# can4vscp_usb_rev_B.net
KiCad netlist of a schematic drawn in EAGLE
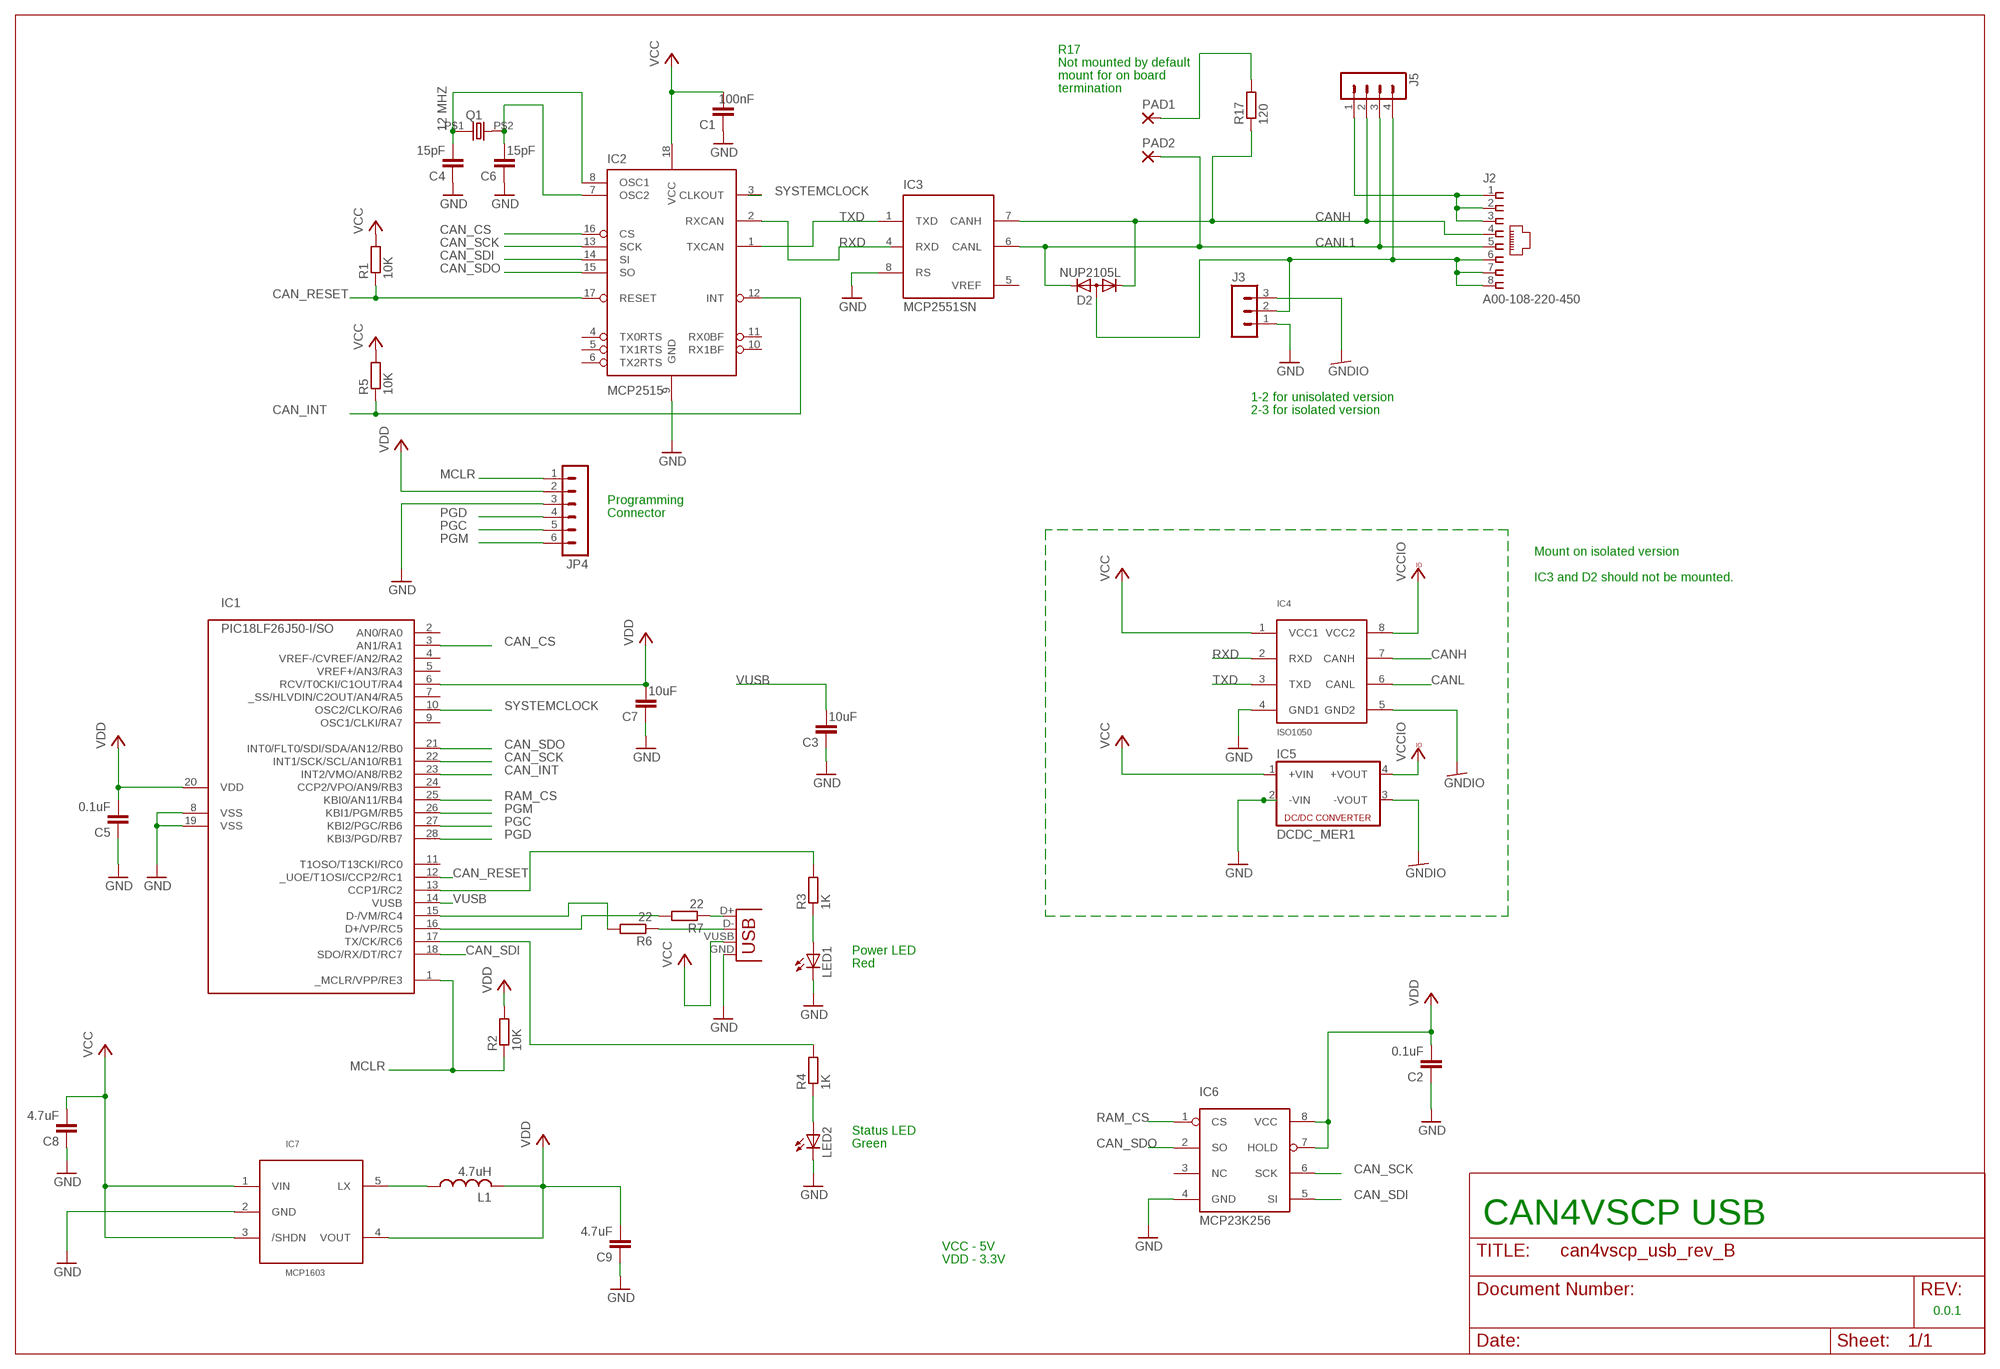
[diagram p0: schematic, sheet 1]

(export (version "E")
  (design (tool "Eeschema 10.0.6"))
  (components
    (comp (ref "C1")
      (value "100nF")
      (footprint "eagle-import:C0805")
      (libsource (lib "eagle-import") (part "C-EUC0805"))
    )
    (comp (ref "C2")
      (value "0.1uF")
      (footprint "eagle-import:C0805")
      (libsource (lib "eagle-import") (part "C-EUC0805"))
    )
    (comp (ref "C3")
      (value "10uF")
      (footprint "eagle-import:C0805")
      (libsource (lib "eagle-import") (part "C-EUC0805"))
    )
    (comp (ref "C4")
      (value "15pF")
      (footprint "eagle-import:C0805")
      (libsource (lib "eagle-import") (part "C-EUC0805"))
    )
    (comp (ref "C5")
      (value "0.1uF")
      (footprint "eagle-import:C0805")
      (libsource (lib "eagle-import") (part "C-EUC0805"))
    )
    (comp (ref "C6")
      (value "15pF")
      (footprint "eagle-import:C0805")
      (libsource (lib "eagle-import") (part "C-EUC0805"))
    )
    (comp (ref "C7")
      (value "10uF")
      (footprint "eagle-import:C0805")
      (libsource (lib "eagle-import") (part "C-EUC0805"))
    )
    (comp (ref "C8")
      (value "4.7uF")
      (footprint "eagle-import:C0805")
      (libsource (lib "eagle-import") (part "C-EUC0805"))
    )
    (comp (ref "C9")
      (value "4.7uF")
      (footprint "eagle-import:C0805")
      (libsource (lib "eagle-import") (part "C-EUC0805"))
    )
    (comp (ref "D2")
      (value "NUP2105L")
      (footprint "eagle-import:SOT23")
      (libsource (lib "eagle-import") (part "DIODE-2CA|ACSOT23"))
    )
    (comp (ref "IC1")
      (value "PIC18LF26J50-I/SO")
      (footprint "eagle-import:SO-28W")
      (libsource (lib "eagle-import") (part "PIC182550-I/SOLF"))
    )
    (comp (ref "IC2")
      (value "MCP2515")
      (footprint "eagle-import:SO-18W")
      (libsource (lib "eagle-import") (part "MCP2515"))
    )
    (comp (ref "IC3")
      (value "MCP2551SN")
      (footprint "eagle-import:SO-08")
      (libsource (lib "eagle-import") (part "MCP2551SN"))
    )
    (comp (ref "IC4")
      (value "ISO1050")
      (footprint "eagle-import:DUB_PSOP")
      (libsource (lib "eagle-import") (part "ISO1050"))
    )
    (comp (ref "IC5")
      (value "DCDC_MER1")
      (footprint "eagle-import:MER1")
      (libsource (lib "eagle-import") (part "DCDC_MER1"))
    )
    (comp (ref "IC6")
      (value "MCP23K256")
      (footprint "eagle-import:SO-8")
      (libsource (lib "eagle-import") (part "MCP23A256"))
    )
    (comp (ref "IC7")
      (value "MCP1603")
      (footprint "eagle-import:SOT23-5L")
      (libsource (lib "eagle-import") (part "MCP1603"))
    )
    (comp (ref "J2")
      (value "A00-108-220-450")
      (footprint "eagle-import:RJ-45")
      (libsource (lib "eagle-import") (part "A00-108-220-450"))
    )
    (comp (ref "J3")
      (value "MA03-1")
      (footprint "eagle-import:MA03-1")
      (libsource (lib "eagle-import") (part "MA03-1"))
    )
    (comp (ref "J4")
      (value "USB-B-S")
      (footprint "eagle-import:USB-B-SMT")
      (libsource (lib "eagle-import") (part "USB-B-S"))
    )
    (comp (ref "J5")
      (value "MA04-1")
      (footprint "eagle-import:MA04-1")
      (libsource (lib "eagle-import") (part "MA04-1"))
    )
    (comp (ref "JP4")
      (value "MA06-1")
      (footprint "eagle-import:MA06-1")
      (libsource (lib "eagle-import") (part "MA06-1"))
    )
    (comp (ref "L1")
      (value "4.7uH")
      (footprint "eagle-import:L2012C")
      (libsource (lib "eagle-import") (part "L-USL2012C"))
    )
    (comp (ref "LED1")
      (value "LEDCHIP-LED0805")
      (footprint "eagle-import:CHIP-LED0805")
      (libsource (lib "eagle-import") (part "LEDCHIP-LED0805"))
    )
    (comp (ref "LED2")
      (value "LEDCHIP-LED0805")
      (footprint "eagle-import:CHIP-LED0805")
      (libsource (lib "eagle-import") (part "LEDCHIP-LED0805"))
    )
    (comp (ref "PAD1")
      (value "1,6/0,8")
      (footprint "eagle-import:1,6_0,8")
      (libsource (lib "eagle-import") (part "1,6/0,8"))
    )
    (comp (ref "PAD2")
      (value "1,6/0,8")
      (footprint "eagle-import:1,6_0,8")
      (libsource (lib "eagle-import") (part "1,6/0,8"))
    )
    (comp (ref "Q1")
      (value "12 MHZ")
      (footprint "eagle-import:9C")
      (libsource (lib "eagle-import") (part "HC-49S"))
    )
    (comp (ref "R1")
      (value "10K")
      (footprint "eagle-import:R0805")
      (libsource (lib "eagle-import") (part "R-EU_R0805"))
    )
    (comp (ref "R2")
      (value "10K")
      (footprint "eagle-import:R0805")
      (libsource (lib "eagle-import") (part "R-EU_R0805"))
    )
    (comp (ref "R3")
      (value "1K")
      (footprint "eagle-import:R0805")
      (libsource (lib "eagle-import") (part "R-EU_R0805"))
    )
    (comp (ref "R4")
      (value "1K")
      (footprint "eagle-import:R0805")
      (libsource (lib "eagle-import") (part "R-EU_R0805"))
    )
    (comp (ref "R5")
      (value "10K")
      (footprint "eagle-import:R0805")
      (libsource (lib "eagle-import") (part "R-EU_R0805"))
    )
    (comp (ref "R6")
      (value "22")
      (footprint "eagle-import:R0805")
      (libsource (lib "eagle-import") (part "R-EU_R0805"))
    )
    (comp (ref "R7")
      (value "22")
      (footprint "eagle-import:R0805")
      (libsource (lib "eagle-import") (part "R-EU_R0805"))
    )
    (comp (ref "R17")
      (value "120")
      (footprint "eagle-import:R0805")
      (libsource (lib "eagle-import") (part "R-EU_R0805"))
    )
  )
  (nets
    (net (code "1") (name "/CANH") (class "Default")
      (node (ref "D2") (pin "1") (pinfunction "K1_1") (pintype "passive"))
      (node (ref "IC3") (pin "7") (pinfunction "CANH_7") (pintype "bidirectional"))
      (node (ref "IC4") (pin "7") (pinfunction "CANH_7") (pintype "bidirectional"))
      (node (ref "J2") (pin "4") (pinfunction "4_4") (pintype "passive"))
      (node (ref "J5") (pin "2") (pinfunction "2_2") (pintype "passive"))
      (node (ref "R17") (pin "1") (pinfunction "1_1") (pintype "passive"))
    )
    (net (code "2") (name "/CANL") (class "Default")
      (node (ref "IC4") (pin "6") (pinfunction "CANL_6") (pintype "bidirectional"))
    )
    (net (code "3") (name "/CANL1") (class "Default")
      (node (ref "D2") (pin "2") (pinfunction "K2_2") (pintype "passive"))
      (node (ref "IC3") (pin "6") (pinfunction "CANL_6") (pintype "bidirectional"))
      (node (ref "J2") (pin "5") (pinfunction "5_5") (pintype "passive"))
      (node (ref "J5") (pin "3") (pinfunction "3_3") (pintype "passive"))
      (node (ref "PAD2") (pin "1") (pinfunction "P_1") (pintype "passive"))
    )
    (net (code "4") (name "/CAN_CS") (class "Default")
      (node (ref "IC1") (pin "3") (pinfunction "AN1/RA1_3") (pintype "bidirectional"))
      (node (ref "IC2") (pin "16") (pinfunction "CS_16") (pintype "input"))
    )
    (net (code "5") (name "/CAN_INT") (class "Default")
      (node (ref "IC1") (pin "23") (pinfunction "INT2/VMO/AN8/RB2_23") (pintype "bidirectional"))
      (node (ref "IC2") (pin "12") (pinfunction "INT_12") (pintype "output"))
      (node (ref "R5") (pin "1") (pinfunction "1_1") (pintype "passive"))
    )
    (net (code "6") (name "/CAN_RESET") (class "Default")
      (node (ref "IC1") (pin "12") (pinfunction "_UOE/T1OSI/CCP2/RC1_12") (pintype "bidirectional"))
      (node (ref "IC2") (pin "17") (pinfunction "RESET_17") (pintype "input"))
      (node (ref "R1") (pin "1") (pinfunction "1_1") (pintype "passive"))
    )
    (net (code "7") (name "/CAN_SCK") (class "Default")
      (node (ref "IC1") (pin "22") (pinfunction "INT1/SCK/SCL/AN10/RB1_22") (pintype "bidirectional"))
      (node (ref "IC2") (pin "13") (pinfunction "SCK_13") (pintype "input"))
      (node (ref "IC6") (pin "6") (pinfunction "SCK_6") (pintype "input"))
    )
    (net (code "8") (name "/CAN_SDI") (class "Default")
      (node (ref "IC1") (pin "18") (pinfunction "SDO/RX/DT/RC7_18") (pintype "bidirectional"))
      (node (ref "IC2") (pin "14") (pinfunction "SI_14") (pintype "input"))
      (node (ref "IC6") (pin "5") (pinfunction "SI_5") (pintype "input"))
    )
    (net (code "9") (name "/CAN_SDO") (class "Default")
      (node (ref "IC1") (pin "21") (pinfunction "INT0/FLT0/SDI/SDA/AN12/RB0_21") (pintype "bidirectional"))
      (node (ref "IC2") (pin "15") (pinfunction "SO_15") (pintype "output"))
      (node (ref "IC6") (pin "2") (pinfunction "SO_2") (pintype "output"))
    )
    (net (code "10") (name "/MCLR") (class "Default")
      (node (ref "IC1") (pin "1") (pinfunction "_MCLR/VPP/RE3_1") (pintype "input"))
      (node (ref "JP4") (pin "1") (pinfunction "1_1") (pintype "passive"))
      (node (ref "R2") (pin "1") (pinfunction "1_1") (pintype "passive"))
    )
    (net (code "11") (name "/PGC") (class "Default")
      (node (ref "IC1") (pin "27") (pinfunction "KBI2/PGC/RB6_27") (pintype "bidirectional"))
      (node (ref "JP4") (pin "5") (pinfunction "5_5") (pintype "passive"))
    )
    (net (code "12") (name "/PGD") (class "Default")
      (node (ref "IC1") (pin "28") (pinfunction "KBI3/PGD/RB7_28") (pintype "bidirectional"))
      (node (ref "JP4") (pin "4") (pinfunction "4_4") (pintype "passive"))
    )
    (net (code "13") (name "/PGM") (class "Default")
      (node (ref "IC1") (pin "26") (pinfunction "KBI1/PGM/RB5_26") (pintype "bidirectional"))
      (node (ref "JP4") (pin "6") (pinfunction "6_6") (pintype "passive"))
    )
    (net (code "14") (name "/RAM_CS") (class "Default")
      (node (ref "IC1") (pin "25") (pinfunction "KBI0/AN11/RB4_25") (pintype "bidirectional"))
      (node (ref "IC6") (pin "1") (pinfunction "CS_1") (pintype "input"))
    )
    (net (code "15") (name "/RXD") (class "Default")
      (node (ref "IC2") (pin "2") (pinfunction "RXCAN_2") (pintype "input"))
      (node (ref "IC4") (pin "2") (pinfunction "RXD_2") (pintype "bidirectional"))
    )
    (net (code "16") (name "/SYSTEMCLOCK") (class "Default")
      (node (ref "IC1") (pin "10") (pinfunction "OSC2/CLKO/RA6_10") (pintype "bidirectional"))
      (node (ref "IC2") (pin "3") (pinfunction "CLKOUT_3") (pintype "output"))
    )
    (net (code "17") (name "/TXD") (class "Default")
      (node (ref "IC2") (pin "1") (pinfunction "TXCAN_1") (pintype "output"))
      (node (ref "IC3") (pin "1") (pinfunction "TXD_1") (pintype "input"))
      (node (ref "IC4") (pin "3") (pinfunction "TXD_3") (pintype "bidirectional"))
    )
    (net (code "18") (name "/VREF") (class "Default")
      (node (ref "IC3") (pin "5") (pinfunction "VREF_5") (pintype "power_in"))
    )
    (net (code "19") (name "/VUSB") (class "Default")
      (node (ref "C3") (pin "2") (pinfunction "2_2") (pintype "passive"))
      (node (ref "IC1") (pin "14") (pinfunction "VUSB_14") (pintype "bidirectional"))
    )
    (net (code "20") (name "GND") (class "Default")
      (node (ref "C1") (pin "1") (pinfunction "1_1") (pintype "passive"))
      (node (ref "C2") (pin "1") (pinfunction "1_1") (pintype "passive"))
      (node (ref "C3") (pin "1") (pinfunction "1_1") (pintype "passive"))
      (node (ref "C4") (pin "1") (pinfunction "1_1") (pintype "passive"))
      (node (ref "C5") (pin "1") (pinfunction "1_1") (pintype "passive"))
      (node (ref "C6") (pin "1") (pinfunction "1_1") (pintype "passive"))
      (node (ref "C7") (pin "1") (pinfunction "1_1") (pintype "passive"))
      (node (ref "C8") (pin "1") (pinfunction "1_1") (pintype "passive"))
      (node (ref "C9") (pin "1") (pinfunction "1_1") (pintype "passive"))
      (node (ref "IC1") (pin "19") (pinfunction "VSS_19") (pintype "power_in"))
      (node (ref "IC1") (pin "8") (pinfunction "VSS_8") (pintype "power_in"))
      (node (ref "IC2") (pin "9") (pinfunction "GND_9") (pintype "power_in"))
      (node (ref "IC3") (pin "8") (pinfunction "RS_8") (pintype "input"))
      (node (ref "IC4") (pin "4") (pinfunction "GND1_4") (pintype "power_in"))
      (node (ref "IC5") (pin "2") (pinfunction "-VIN_2") (pintype "passive"))
      (node (ref "IC6") (pin "4") (pinfunction "GND_4") (pintype "power_in"))
      (node (ref "IC7") (pin "2") (pinfunction "GND_2") (pintype "power_in"))
      (node (ref "J3") (pin "1") (pinfunction "1_1") (pintype "passive"))
      (node (ref "J4") (pin "GND") (pinfunction "GND_GND") (pintype "bidirectional"))
      (node (ref "JP4") (pin "3") (pinfunction "3_3") (pintype "passive"))
      (node (ref "LED1") (pin "C") (pinfunction "C_C") (pintype "passive"))
      (node (ref "LED2") (pin "C") (pinfunction "C_C") (pintype "passive"))
    )
    (net (code "21") (name "GNDIO") (class "Default")
      (node (ref "IC4") (pin "5") (pinfunction "GND2_5") (pintype "power_in"))
      (node (ref "IC5") (pin "3") (pinfunction "-VOUT_3") (pintype "passive"))
      (node (ref "J3") (pin "3") (pinfunction "3_3") (pintype "passive"))
    )
    (net (code "22") (name "Net-(D2-A)") (class "Default")
      (node (ref "D2") (pin "3") (pinfunction "A_3") (pintype "passive"))
      (node (ref "J2") (pin "6") (pinfunction "6_6") (pintype "passive"))
      (node (ref "J2") (pin "7") (pinfunction "7_7") (pintype "passive"))
      (node (ref "J2") (pin "8") (pinfunction "8_8") (pintype "passive"))
      (node (ref "J3") (pin "2") (pinfunction "2_2") (pintype "passive"))
      (node (ref "J5") (pin "4") (pinfunction "4_4") (pintype "passive"))
    )
    (net (code "23") (name "Net-(IC1-CCP1{slash}RC2)") (class "Default")
      (node (ref "IC1") (pin "13") (pinfunction "CCP1/RC2_13") (pintype "bidirectional"))
      (node (ref "R3") (pin "2") (pinfunction "2_2") (pintype "passive"))
    )
    (net (code "24") (name "Net-(IC1-D+{slash}VP{slash}RC5)") (class "Default")
      (node (ref "IC1") (pin "16") (pinfunction "D+/VP/RC5_16") (pintype "bidirectional"))
      (node (ref "R7") (pin "2") (pinfunction "2_2") (pintype "passive"))
    )
    (net (code "25") (name "Net-(IC1-D-{slash}VM{slash}RC4)") (class "Default")
      (node (ref "IC1") (pin "15") (pinfunction "D-/VM/RC4_15") (pintype "bidirectional"))
      (node (ref "R6") (pin "2") (pinfunction "2_2") (pintype "passive"))
    )
    (net (code "26") (name "Net-(IC1-TX{slash}CK{slash}RC6)") (class "Default")
      (node (ref "IC1") (pin "17") (pinfunction "TX/CK/RC6_17") (pintype "bidirectional"))
      (node (ref "R4") (pin "2") (pinfunction "2_2") (pintype "passive"))
    )
    (net (code "27") (name "Net-(IC2-OSC1)") (class "Default")
      (node (ref "C4") (pin "2") (pinfunction "2_2") (pintype "passive"))
      (node (ref "IC2") (pin "8") (pinfunction "OSC1_8") (pintype "input"))
      (node (ref "Q1") (pin "P$1") (pinfunction "1_P$1") (pintype "passive"))
    )
    (net (code "28") (name "Net-(IC2-OSC2)") (class "Default")
      (node (ref "C6") (pin "2") (pinfunction "2_2") (pintype "passive"))
      (node (ref "IC2") (pin "7") (pinfunction "OSC2_7") (pintype "output"))
      (node (ref "Q1") (pin "P$2") (pinfunction "2_P$2") (pintype "passive"))
    )
    (net (code "29") (name "Net-(IC7-LX)") (class "Default")
      (node (ref "IC7") (pin "5") (pinfunction "LX_5") (pintype "bidirectional"))
      (node (ref "L1") (pin "1") (pinfunction "1_1") (pintype "passive"))
    )
    (net (code "30") (name "Net-(J2-Pad1)") (class "Default")
      (node (ref "J2") (pin "1") (pinfunction "1_1") (pintype "passive"))
      (node (ref "J2") (pin "2") (pinfunction "2_2") (pintype "passive"))
      (node (ref "J2") (pin "3") (pinfunction "3_3") (pintype "passive"))
      (node (ref "J5") (pin "1") (pinfunction "1_1") (pintype "passive"))
    )
    (net (code "31") (name "Net-(J4-PadD+)") (class "Default")
      (node (ref "J4") (pin "D+") (pinfunction "D+_D+") (pintype "bidirectional"))
      (node (ref "R7") (pin "1") (pinfunction "1_1") (pintype "passive"))
    )
    (net (code "32") (name "Net-(J4-PadD-)") (class "Default")
      (node (ref "J4") (pin "D-") (pinfunction "D-_D-") (pintype "bidirectional"))
      (node (ref "R6") (pin "1") (pinfunction "1_1") (pintype "passive"))
    )
    (net (code "33") (name "Net-(LED1-PadA)") (class "Default")
      (node (ref "LED1") (pin "A") (pinfunction "A_A") (pintype "passive"))
      (node (ref "R3") (pin "1") (pinfunction "1_1") (pintype "passive"))
    )
    (net (code "34") (name "Net-(LED2-PadA)") (class "Default")
      (node (ref "LED2") (pin "A") (pinfunction "A_A") (pintype "passive"))
      (node (ref "R4") (pin "1") (pinfunction "1_1") (pintype "passive"))
    )
    (net (code "35") (name "Net-(PAD1-P)") (class "Default")
      (node (ref "PAD1") (pin "1") (pinfunction "P_1") (pintype "passive"))
      (node (ref "R17") (pin "2") (pinfunction "2_2") (pintype "passive"))
    )
    (net (code "36") (name "VCC") (class "Default")
      (node (ref "C1") (pin "2") (pinfunction "2_2") (pintype "passive"))
      (node (ref "C8") (pin "2") (pinfunction "2_2") (pintype "passive"))
      (node (ref "IC2") (pin "18") (pinfunction "VCC_18") (pintype "power_in"))
      (node (ref "IC4") (pin "1") (pinfunction "VCC1_1") (pintype "power_in"))
      (node (ref "IC5") (pin "1") (pinfunction "+VIN_1") (pintype "passive"))
      (node (ref "IC7") (pin "1") (pinfunction "VIN_1") (pintype "bidirectional"))
      (node (ref "IC7") (pin "3") (pinfunction "/SHDN_3") (pintype "bidirectional"))
      (node (ref "J4") (pin "VUSB") (pinfunction "VBUS_VUSB") (pintype "bidirectional"))
      (node (ref "R1") (pin "2") (pinfunction "2_2") (pintype "passive"))
      (node (ref "R5") (pin "2") (pinfunction "2_2") (pintype "passive"))
    )
    (net (code "37") (name "VCCIO") (class "Default")
      (node (ref "IC4") (pin "8") (pinfunction "VCC2_8") (pintype "power_in"))
      (node (ref "IC5") (pin "4") (pinfunction "+VOUT_4") (pintype "passive"))
    )
    (net (code "38") (name "VDD") (class "Default")
      (node (ref "C2") (pin "2") (pinfunction "2_2") (pintype "passive"))
      (node (ref "C5") (pin "2") (pinfunction "2_2") (pintype "passive"))
      (node (ref "C7") (pin "2") (pinfunction "2_2") (pintype "passive"))
      (node (ref "C9") (pin "2") (pinfunction "2_2") (pintype "passive"))
      (node (ref "IC1") (pin "20") (pinfunction "VDD_20") (pintype "power_in"))
      (node (ref "IC1") (pin "6") (pinfunction "RCV/T0CKI/C1OUT/RA4_6") (pintype "bidirectional"))
      (node (ref "IC6") (pin "7") (pinfunction "HOLD_7") (pintype "input"))
      (node (ref "IC6") (pin "8") (pinfunction "VCC_8") (pintype "power_in"))
      (node (ref "IC7") (pin "4") (pinfunction "VOUT_4") (pintype "bidirectional"))
      (node (ref "JP4") (pin "2") (pinfunction "2_2") (pintype "passive"))
      (node (ref "L1") (pin "2") (pinfunction "2_2") (pintype "passive"))
      (node (ref "R2") (pin "2") (pinfunction "2_2") (pintype "passive"))
    )
    (net (code "39") (name "unconnected-(IC1-AN0{slash}RA0-Pad2)") (class "Default")
      (node (ref "IC1") (pin "2") (pinfunction "AN0/RA0_2") (pintype "bidirectional"))
    )
    (net (code "40") (name "unconnected-(IC1-CCP2{slash}VPO{slash}AN9{slash}RB3-Pad24)") (class "Default")
      (node (ref "IC1") (pin "24") (pinfunction "CCP2/VPO/AN9/RB3_24") (pintype "bidirectional"))
    )
    (net (code "41") (name "unconnected-(IC1-OSC1{slash}CLKI{slash}RA7-Pad9)") (class "Default")
      (node (ref "IC1") (pin "9") (pinfunction "OSC1/CLKI/RA7_9") (pintype "bidirectional"))
    )
    (net (code "42") (name "unconnected-(IC1-T1OSO{slash}T13CKI{slash}RC0-Pad11)") (class "Default")
      (node (ref "IC1") (pin "11") (pinfunction "T1OSO/T13CKI/RC0_11") (pintype "bidirectional"))
    )
    (net (code "43") (name "unconnected-(IC1-VREF+{slash}AN3{slash}RA3-Pad5)") (class "Default")
      (node (ref "IC1") (pin "5") (pinfunction "VREF+/AN3/RA3_5") (pintype "bidirectional"))
    )
    (net (code "44") (name "unconnected-(IC1-VREF-{slash}CVREF{slash}AN2{slash}RA2-Pad4)") (class "Default")
      (node (ref "IC1") (pin "4") (pinfunction "VREF-/CVREF/AN2/RA2_4") (pintype "bidirectional"))
    )
    (net (code "45") (name "unconnected-(IC1-_SS{slash}HLVDIN{slash}C2OUT{slash}AN4{slash}RA5-Pad7)") (class "Default")
      (node (ref "IC1") (pin "7") (pinfunction "_SS/HLVDIN/C2OUT/AN4/RA5_7") (pintype "bidirectional"))
    )
    (net (code "46") (name "unconnected-(IC2-RX0BF-Pad11)") (class "Default")
      (node (ref "IC2") (pin "11") (pinfunction "RX0BF_11") (pintype "output"))
    )
    (net (code "47") (name "unconnected-(IC2-RX1BF-Pad10)") (class "Default")
      (node (ref "IC2") (pin "10") (pinfunction "RX1BF_10") (pintype "output"))
    )
    (net (code "48") (name "unconnected-(IC2-TX0RTS-Pad4)") (class "Default")
      (node (ref "IC2") (pin "4") (pinfunction "TX0RTS_4") (pintype "input"))
    )
    (net (code "49") (name "unconnected-(IC2-TX1RTS-Pad5)") (class "Default")
      (node (ref "IC2") (pin "5") (pinfunction "TX1RTS_5") (pintype "input"))
    )
    (net (code "50") (name "unconnected-(IC2-TX2RTS-Pad6)") (class "Default")
      (node (ref "IC2") (pin "6") (pinfunction "TX2RTS_6") (pintype "input"))
    )
    (net (code "51") (name "unconnected-(IC3A-RXD-Pad4)") (class "Default")
      (node (ref "IC3") (pin "4") (pinfunction "RXD_4") (pintype "output"))
    )
    (net (code "52") (name "unconnected-(IC6-NC-Pad3)") (class "Default")
      (node (ref "IC6") (pin "3") (pinfunction "NC_3") (pintype "no_connect"))
    )
  )
)
